# 300_CDH_RS422.net
KiCad netlist of a schematic drawn in Altium Designer
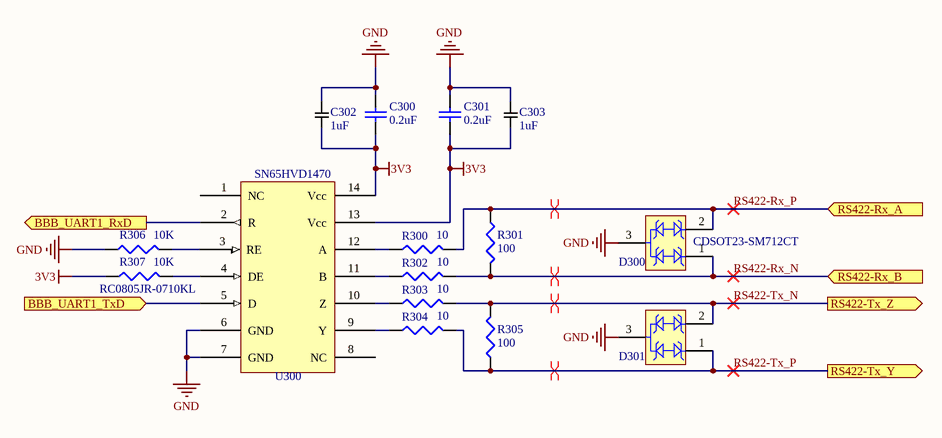
[diagram p0: 300_CDH_RS422.SchDoc]

(export (version "E")
  (design (tool "Eeschema 10.0.6"))
  (components
    (comp (ref "C300")
      (value "0.2uF")
      (footprint "IMPERIAL0805_CAPACITOR")
      (description "0.2uF Capacitor")
      (fields (field (name "PUBLISHER") "Altium Limited"))
      (libsource (lib "OASIS_COMPONENTS_SYMBOLS") (part "GCM219R71C204JA37J"))
    )
    (comp (ref "C301")
      (value "0.2uF")
      (footprint "IMPERIAL0805_CAPACITOR")
      (description "0.2uF Capacitor")
      (fields (field (name "PUBLISHER") "Altium Limited"))
      (libsource (lib "OASIS_COMPONENTS_SYMBOLS") (part "GCM219R71C204JA37J"))
    )
    (comp (ref "C302")
      (value "1uF")
      (footprint "IMPERIAL0603_Capacitor")
      (description "1 uF Capacitor")
      (libsource (lib "OASIS_COMPONENTS_SYMBOLS") (part "TMK107BLD105KA-T"))
    )
    (comp (ref "C303")
      (value "1uF")
      (footprint "IMPERIAL0603_Capacitor")
      (description "1 uF Capacitor")
      (libsource (lib "OASIS_COMPONENTS_SYMBOLS") (part "TMK107BLD105KA-T"))
    )
    (comp (ref "D300")
      (value "CDSOT23-SM712")
      (footprint "BOUR-SOT23-3_V")
      (description "TVS Diode, 17 A Ipp, -55 to 150 degC, 3-Pin SOT23, RoHS, Tape and Reel")
      (fields (field (name "MANUFACTURER") "Bourns") (field (name "OTHER NAMES") "CDSOT23-SM712CT"))
      (libsource (lib "OASIS_COMPONENTS_SYMBOLS") (part "CDSOT23-SM712"))
    )
    (comp (ref "D301")
      (value "CDSOT23-SM712")
      (footprint "BOUR-SOT23-3_V")
      (description "TVS Diode, 17 A Ipp, -55 to 150 degC, 3-Pin SOT23, RoHS, Tape and Reel")
      (fields (field (name "MANUFACTURER") "Bourns"))
      (libsource (lib "OASIS_COMPONENTS_SYMBOLS") (part "CDSOT23-SM712"))
    )
    (comp (ref "R300")
      (value "10")
      (footprint "Imperial1206_RES")
      (description "10 Ohm Resistor, RS-422 shockproof resistor")
      (fields (field (name "Comment") "10 Ohm Resistor") (field (name "PUBLISHER") "Altium Limited"))
      (libsource (lib "OASIS_COMPONENTS_SYMBOLS") (part "SR732BTTE10R0F"))
    )
    (comp (ref "R301")
      (value "100")
      (footprint "Imperial0805_RES")
      (description "100 Ohm resistor, RS422 Terminating Resistor")
      (fields (field (name "Comment") "100 Ohm Resistor") (field (name "PUBLISHER") "Altium Limited"))
      (libsource (lib "OASIS_COMPONENTS_SYMBOLS") (part "SR0805FR-47100RL"))
    )
    (comp (ref "R302")
      (value "10")
      (footprint "Imperial1206_RES")
      (description "10 Ohm Resistor, RS-422 shockproof resistor")
      (fields (field (name "Comment") "10 Ohm Resistor") (field (name "PUBLISHER") "Altium Limited"))
      (libsource (lib "OASIS_COMPONENTS_SYMBOLS") (part "SR732BTTE10R0F"))
    )
    (comp (ref "R303")
      (value "10")
      (footprint "Imperial1206_RES")
      (description "10 Ohm Resistor, RS-422 shockproof resistor")
      (fields (field (name "Comment") "10 Ohm Resistor") (field (name "PUBLISHER") "Altium Limited"))
      (libsource (lib "OASIS_COMPONENTS_SYMBOLS") (part "SR732BTTE10R0F"))
    )
    (comp (ref "R304")
      (value "10")
      (footprint "Imperial1206_RES")
      (description "10 Ohm Resistor, RS-422 shockproof resistor")
      (fields (field (name "Comment") "10 Ohm Resistor") (field (name "PUBLISHER") "Altium Limited"))
      (libsource (lib "OASIS_COMPONENTS_SYMBOLS") (part "SR732BTTE10R0F"))
    )
    (comp (ref "R305")
      (value "100")
      (footprint "Imperial0805_RES")
      (description "100 Ohm resistor, RS422 Terminating Resistor")
      (fields (field (name "Comment") "100 Ohm Resistor") (field (name "PUBLISHER") "Altium Limited"))
      (libsource (lib "OASIS_COMPONENTS_SYMBOLS") (part "SR0805FR-47100RL"))
    )
    (comp (ref "R306")
      (value "10K")
      (footprint "Imperial0805_RES")
      (description "10K resistor, 1/8W, 0805 Imperial")
      (fields (field (name "MANUFACTURER_PART_NUMBER") "RC0805JR-0710KL"))
      (libsource (lib "OASIS_COMPONENTS_SYMBOLS") (part "RC0805JR-0710KL"))
    )
    (comp (ref "R307")
      (value "RC0805JR-0710KL")
      (footprint "Imperial0805_RES")
      (description "10K resistor, 1/8W, 0805 Imperial")
      (fields (field (name "ALTIUM_VALUE") "10K"))
      (libsource (lib "OASIS_COMPONENTS_SYMBOLS") (part "RC0805JR-0710KL"))
    )
    (comp (ref "U300")
      (value "SN65HVD1470D")
      (footprint "SOIC127P590X175-14M")
      (description "RS-422 line driver IC")
      (fields (field (name "GENERIC PART NUMBER") "SN65HVD1470"))
      (libsource (lib "OASIS_COMPONENTS_SYMBOLS") (part "SN65HVD1470D"))
    )
  )
  (nets
    (net (code "1") (name "/BBB_UART1_RxD") (class "Default")
      (node (ref "U300") (pin "2") (pinfunction "R_2") (pintype "output"))
    )
    (net (code "2") (name "/BBB_UART1_TxD") (class "Default")
      (node (ref "U300") (pin "5") (pinfunction "D_5") (pintype "input"))
    )
    (net (code "3") (name "/RS422-Rx_A") (class "Default")
      (node (ref "D300") (pin "2") (pinfunction "2_2") (pintype "passive"))
      (node (ref "R300") (pin "2") (pinfunction "2_2") (pintype "passive"))
      (node (ref "R301") (pin "1") (pinfunction "1_1") (pintype "passive"))
    )
    (net (code "4") (name "/RS422-Rx_B") (class "Default")
      (node (ref "D300") (pin "1") (pinfunction "1_1") (pintype "passive"))
      (node (ref "R301") (pin "2") (pinfunction "2_2") (pintype "passive"))
      (node (ref "R302") (pin "2") (pinfunction "2_2") (pintype "passive"))
    )
    (net (code "9") (name "/RS422-Tx_Y") (class "Default")
      (node (ref "D301") (pin "1") (pinfunction "1_1") (pintype "passive"))
      (node (ref "R304") (pin "2") (pinfunction "2_2") (pintype "passive"))
      (node (ref "R305") (pin "1") (pinfunction "1_1") (pintype "passive"))
    )
    (net (code "10") (name "/RS422-Tx_Z") (class "Default")
      (node (ref "D301") (pin "2") (pinfunction "2_2") (pintype "passive"))
      (node (ref "R303") (pin "2") (pinfunction "2_2") (pintype "passive"))
      (node (ref "R305") (pin "2") (pinfunction "2_2") (pintype "passive"))
    )
    (net (code "11") (name "3V3") (class "Default")
      (node (ref "C300") (pin "1") (pinfunction "1_1") (pintype "passive"))
      (node (ref "C301") (pin "1") (pinfunction "1_1") (pintype "passive"))
      (node (ref "C302") (pin "1") (pinfunction "1_1") (pintype "passive"))
      (node (ref "C303") (pin "1") (pinfunction "1_1") (pintype "passive"))
      (node (ref "R307") (pin "1") (pinfunction "1_1") (pintype "passive"))
      (node (ref "U300") (pin "13") (pinfunction "Vcc_13") (pintype "passive"))
      (node (ref "U300") (pin "14") (pinfunction "Vcc_14") (pintype "power_in"))
    )
    (net (code "12") (name "GND") (class "Default")
      (node (ref "C300") (pin "2") (pinfunction "2_2") (pintype "passive"))
      (node (ref "C301") (pin "2") (pinfunction "2_2") (pintype "passive"))
      (node (ref "C302") (pin "2") (pinfunction "2_2") (pintype "passive"))
      (node (ref "C303") (pin "2") (pinfunction "2_2") (pintype "passive"))
      (node (ref "D300") (pin "3") (pinfunction "3_3") (pintype "passive"))
      (node (ref "D301") (pin "3") (pinfunction "3_3") (pintype "passive"))
      (node (ref "R306") (pin "1") (pinfunction "1_1") (pintype "passive"))
      (node (ref "U300") (pin "6") (pinfunction "GND_6") (pintype "power_in"))
      (node (ref "U300") (pin "7") (pinfunction "GND_7") (pintype "power_in"))
    )
    (net (code "13") (name "Net-(U300-A)") (class "Default")
      (node (ref "R300") (pin "1") (pinfunction "1_1") (pintype "passive"))
      (node (ref "U300") (pin "12") (pinfunction "A_12") (pintype "passive"))
    )
    (net (code "14") (name "Net-(U300-B)") (class "Default")
      (node (ref "R302") (pin "1") (pinfunction "1_1") (pintype "passive"))
      (node (ref "U300") (pin "11") (pinfunction "B_11") (pintype "passive"))
    )
    (net (code "15") (name "Net-(U300-DE)") (class "Default")
      (node (ref "R307") (pin "2") (pinfunction "2_2") (pintype "passive"))
      (node (ref "U300") (pin "4") (pinfunction "DE_4") (pintype "input"))
    )
    (net (code "16") (name "Net-(U300-RE)") (class "Default")
      (node (ref "R306") (pin "2") (pinfunction "2_2") (pintype "passive"))
      (node (ref "U300") (pin "3") (pinfunction "RE_3") (pintype "input"))
    )
    (net (code "17") (name "Net-(U300-Y)") (class "Default")
      (node (ref "R304") (pin "1") (pinfunction "1_1") (pintype "passive"))
      (node (ref "U300") (pin "9") (pinfunction "Y_9") (pintype "passive"))
    )
    (net (code "18") (name "Net-(U300-Z)") (class "Default")
      (node (ref "R303") (pin "1") (pinfunction "1_1") (pintype "passive"))
      (node (ref "U300") (pin "10") (pinfunction "Z_10") (pintype "passive"))
    )
    (net (code "19") (name "unconnected-(U300-NC-Pad1)") (class "Default")
      (node (ref "U300") (pin "1") (pinfunction "NC_1") (pintype "tri_state"))
    )
    (net (code "20") (name "unconnected-(U300-NC-Pad8)") (class "Default")
      (node (ref "U300") (pin "8") (pinfunction "NC_8") (pintype "passive"))
    )
  )
)
